# FSR_Array_Sch.net
KiCad netlist of a schematic drawn in Altium Designer
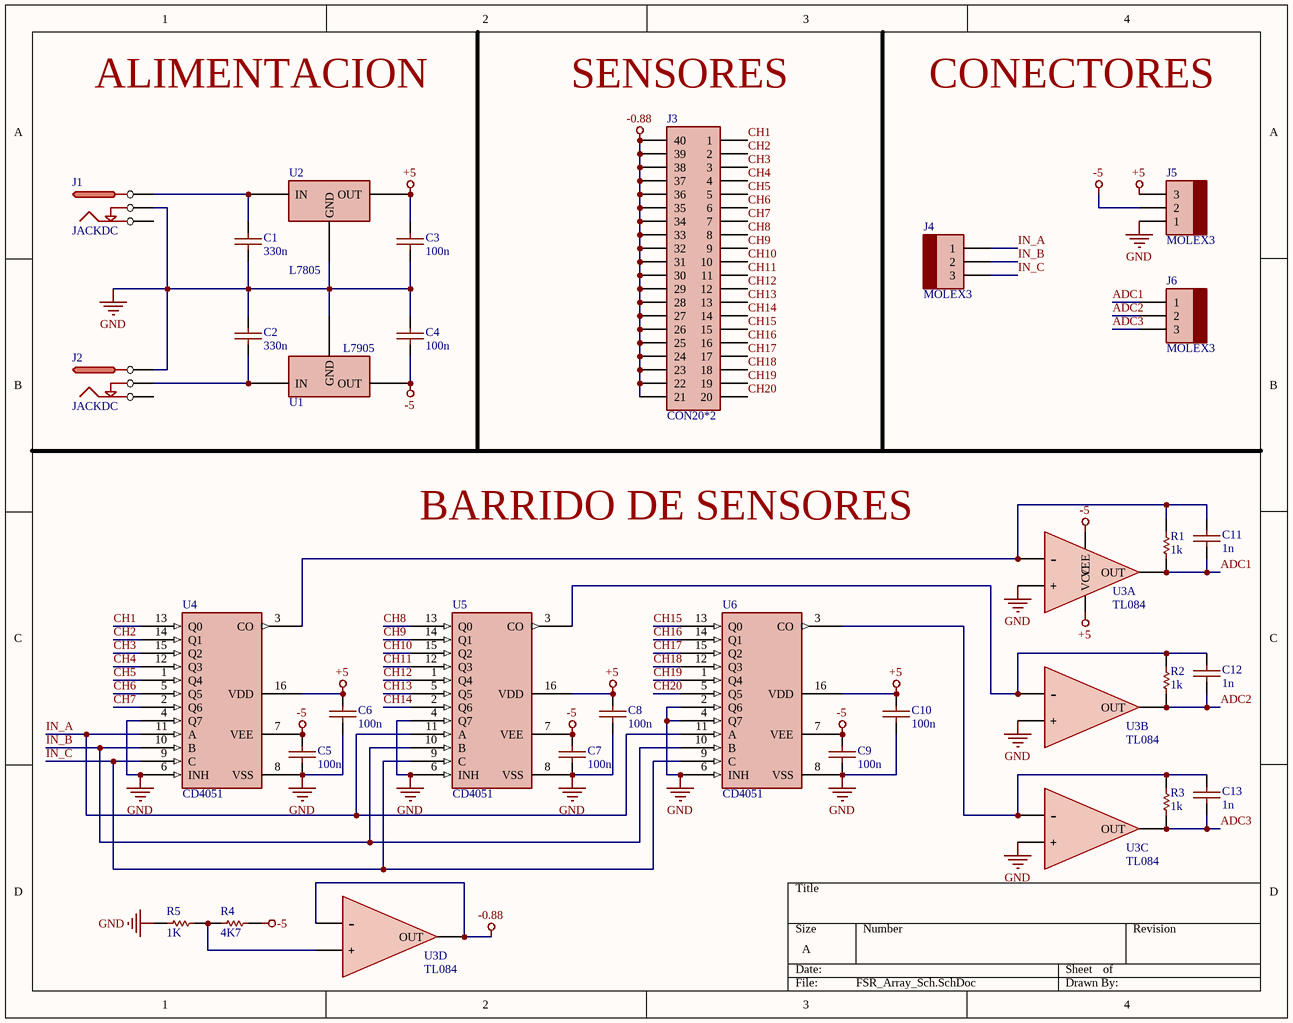
[diagram p0: FSR_Array_Sch.SchDoc]

(export (version "E")
  (design (tool "Eeschema 10.0.6"))
  (components
    (comp (ref "C1") (value "330n") (footprint "0805") (libsource (lib "SchLib_Recinto") (part "CAP")))
    (comp (ref "C2") (value "330n") (footprint "0805") (libsource (lib "SchLib_Recinto") (part "CAP")))
    (comp (ref "C3") (value "100n") (footprint "0805") (libsource (lib "SchLib_Recinto") (part "CAP")))
    (comp (ref "C4") (value "100n") (footprint "0805") (libsource (lib "SchLib_Recinto") (part "CAP")))
    (comp (ref "C5") (value "100n") (footprint "0805") (libsource (lib "SchLib_Recinto") (part "CAP")))
    (comp (ref "C6") (value "100n") (footprint "0805") (libsource (lib "SchLib_Recinto") (part "CAP")))
    (comp (ref "C7") (value "100n") (footprint "0805") (libsource (lib "SchLib_Recinto") (part "CAP")))
    (comp (ref "C8") (value "100n") (footprint "0805") (libsource (lib "SchLib_Recinto") (part "CAP")))
    (comp (ref "C9") (value "100n") (footprint "0805") (libsource (lib "SchLib_Recinto") (part "CAP")))
    (comp (ref "C10") (value "100n") (footprint "0805") (libsource (lib "SchLib_Recinto") (part "CAP")))
    (comp (ref "C11") (value "1n") (footprint "0805") (libsource (lib "SchLib_Recinto") (part "CAP")))
    (comp (ref "C12") (value "1n") (footprint "0805") (libsource (lib "SchLib_Recinto") (part "CAP")))
    (comp (ref "C13") (value "1n") (footprint "0805") (libsource (lib "SchLib_Recinto") (part "CAP")))
    (comp (ref "J1") (value "JACKDC") (footprint "JACKDC") (libsource (lib "SchLib_Recinto") (part "JACKDC")))
    (comp (ref "J2") (value "JACKDC") (footprint "JACKDC") (libsource (lib "SchLib_Recinto") (part "JACKDC")))
    (comp (ref "J3")
      (value "CON20*2")
      (footprint "SIP20*2")
      (libsource (lib "SchLib_Recinto") (part "CON20*2"))
    )
    (comp (ref "J4") (value "MOLEX3") (footprint "MOLEX3") (libsource (lib "SchLib_Recinto") (part "MOLEX3")))
    (comp (ref "J5") (value "MOLEX3") (footprint "MOLEX3") (libsource (lib "") (part "MOLEX3_2")))
    (comp (ref "J6") (value "MOLEX3") (footprint "MOLEX3") (libsource (lib "") (part "MOLEX3_1")))
    (comp (ref "R1") (value "1k") (footprint "0805") (libsource (lib "SchLib_Recinto") (part "RES")))
    (comp (ref "R2") (value "1k") (footprint "0805") (libsource (lib "SchLib_Recinto") (part "RES")))
    (comp (ref "R3") (value "1k") (footprint "0805") (libsource (lib "SchLib_Recinto") (part "RES")))
    (comp (ref "R4") (value "4K7") (footprint "0805") (libsource (lib "SchLib_Recinto") (part "RES")))
    (comp (ref "R5") (value "1K") (footprint "0805") (libsource (lib "SchLib_Recinto") (part "RES")))
    (comp (ref "U1")
      (value "L7905")
      (footprint "TO-220 V")
      (libsource (lib "SchLib_Recinto") (part "LM7905"))
    )
    (comp (ref "U2") (value "L7805") (footprint "TO-220 V") (libsource (lib "SchLib_Recinto") (part "L7805")))
    (comp (ref "U3") (value "TL084") (footprint "SOIC-14") (libsource (lib "SchLib_Recinto") (part "TL084")))
    (comp (ref "U4") (value "CD4051") (footprint "CD4051") (libsource (lib "SchLib_Recinto") (part "CD4051")))
    (comp (ref "U5") (value "CD4051") (footprint "CD4051") (libsource (lib "SchLib_Recinto") (part "CD4051")))
    (comp (ref "U6") (value "CD4051") (footprint "CD4051") (libsource (lib "SchLib_Recinto") (part "CD4051")))
  )
  (nets
    (net (code "1") (name "+5") (class "Default")
      (node (ref "C10") (pin "1") (pintype "passive"))
      (node (ref "C3") (pin "1") (pintype "passive"))
      (node (ref "C6") (pin "1") (pintype "passive"))
      (node (ref "C8") (pin "1") (pintype "passive"))
      (node (ref "J5") (pin "3") (pinfunction "3_3") (pintype "passive"))
      (node (ref "U2") (pin "3") (pinfunction "OUT_3") (pintype "passive"))
      (node (ref "U3") (pin "4") (pinfunction "VCC_4") (pintype "passive"))
      (node (ref "U4") (pin "16") (pinfunction "VDD_16") (pintype "power_in"))
      (node (ref "U5") (pin "16") (pinfunction "VDD_16") (pintype "power_in"))
      (node (ref "U6") (pin "16") (pinfunction "VDD_16") (pintype "power_in"))
    )
    (net (code "2") (name "-0.88") (class "Default")
      (node (ref "J3") (pin "21") (pinfunction "21_21") (pintype "passive"))
      (node (ref "J3") (pin "22") (pinfunction "22_22") (pintype "passive"))
      (node (ref "J3") (pin "23") (pinfunction "23_23") (pintype "passive"))
      (node (ref "J3") (pin "24") (pinfunction "24_24") (pintype "passive"))
      (node (ref "J3") (pin "25") (pinfunction "25_25") (pintype "passive"))
      (node (ref "J3") (pin "26") (pinfunction "26_26") (pintype "passive"))
      (node (ref "J3") (pin "27") (pinfunction "27_27") (pintype "passive"))
      (node (ref "J3") (pin "28") (pinfunction "28_28") (pintype "passive"))
      (node (ref "J3") (pin "29") (pinfunction "29_29") (pintype "passive"))
      (node (ref "J3") (pin "30") (pinfunction "30_30") (pintype "passive"))
      (node (ref "J3") (pin "31") (pinfunction "31_31") (pintype "passive"))
      (node (ref "J3") (pin "32") (pinfunction "32_32") (pintype "passive"))
      (node (ref "J3") (pin "33") (pinfunction "33_33") (pintype "passive"))
      (node (ref "J3") (pin "34") (pinfunction "34_34") (pintype "passive"))
      (node (ref "J3") (pin "35") (pinfunction "35_35") (pintype "passive"))
      (node (ref "J3") (pin "36") (pinfunction "36_36") (pintype "passive"))
      (node (ref "J3") (pin "37") (pinfunction "37_37") (pintype "passive"))
      (node (ref "J3") (pin "38") (pinfunction "38_38") (pintype "passive"))
      (node (ref "J3") (pin "39") (pinfunction "39_39") (pintype "passive"))
      (node (ref "J3") (pin "40") (pinfunction "40_40") (pintype "passive"))
      (node (ref "U3") (pin "13") (pinfunction "-_13") (pintype "passive"))
      (node (ref "U3") (pin "14") (pinfunction "OUT_14") (pintype "passive"))
    )
    (net (code "3") (name "-5") (class "Default")
      (node (ref "C4") (pin "2") (pintype "passive"))
      (node (ref "C5") (pin "1") (pintype "passive"))
      (node (ref "C7") (pin "1") (pintype "passive"))
      (node (ref "C9") (pin "1") (pintype "passive"))
      (node (ref "J5") (pin "2") (pinfunction "2_2") (pintype "passive"))
      (node (ref "R4") (pin "1") (pinfunction "1_1") (pintype "passive"))
      (node (ref "U1") (pin "3") (pinfunction "OUT_3") (pintype "passive"))
      (node (ref "U3") (pin "11") (pinfunction "VEE_11") (pintype "passive"))
      (node (ref "U4") (pin "7") (pinfunction "VEE_7") (pintype "power_in"))
      (node (ref "U5") (pin "7") (pinfunction "VEE_7") (pintype "power_in"))
      (node (ref "U6") (pin "7") (pinfunction "VEE_7") (pintype "power_in"))
    )
    (net (code "4") (name "/ADC1") (class "Default")
      (node (ref "C11") (pin "2") (pintype "passive"))
      (node (ref "J6") (pin "1") (pinfunction "1_1") (pintype "passive"))
      (node (ref "R1") (pin "1") (pinfunction "1_1") (pintype "passive"))
      (node (ref "U3") (pin "1") (pinfunction "OUT_1") (pintype "passive"))
    )
    (net (code "5") (name "/ADC2") (class "Default")
      (node (ref "C12") (pin "2") (pintype "passive"))
      (node (ref "J6") (pin "2") (pinfunction "2_2") (pintype "passive"))
      (node (ref "R2") (pin "1") (pinfunction "1_1") (pintype "passive"))
      (node (ref "U3") (pin "7") (pinfunction "OUT_7") (pintype "passive"))
    )
    (net (code "6") (name "/ADC3") (class "Default")
      (node (ref "C13") (pin "2") (pintype "passive"))
      (node (ref "J6") (pin "3") (pinfunction "3_3") (pintype "passive"))
      (node (ref "R3") (pin "1") (pinfunction "1_1") (pintype "passive"))
      (node (ref "U3") (pin "8") (pinfunction "OUT_8") (pintype "passive"))
    )
    (net (code "7") (name "/CH1") (class "Default")
      (node (ref "J3") (pin "1") (pinfunction "1_1") (pintype "passive"))
      (node (ref "U4") (pin "13") (pinfunction "Q0_13") (pintype "input"))
    )
    (net (code "8") (name "/CH2") (class "Default")
      (node (ref "J3") (pin "2") (pinfunction "2_2") (pintype "passive"))
      (node (ref "U4") (pin "14") (pinfunction "Q1_14") (pintype "input"))
    )
    (net (code "9") (name "/CH3") (class "Default")
      (node (ref "J3") (pin "3") (pinfunction "3_3") (pintype "passive"))
      (node (ref "U4") (pin "15") (pinfunction "Q2_15") (pintype "input"))
    )
    (net (code "10") (name "/CH4") (class "Default")
      (node (ref "J3") (pin "4") (pinfunction "4_4") (pintype "passive"))
      (node (ref "U4") (pin "12") (pinfunction "Q3_12") (pintype "input"))
    )
    (net (code "11") (name "/CH5") (class "Default")
      (node (ref "J3") (pin "5") (pinfunction "5_5") (pintype "passive"))
      (node (ref "U4") (pin "1") (pinfunction "Q4_1") (pintype "input"))
    )
    (net (code "12") (name "/CH6") (class "Default")
      (node (ref "J3") (pin "6") (pinfunction "6_6") (pintype "passive"))
      (node (ref "U4") (pin "5") (pinfunction "Q5_5") (pintype "input"))
    )
    (net (code "13") (name "/CH7") (class "Default")
      (node (ref "J3") (pin "7") (pinfunction "7_7") (pintype "passive"))
      (node (ref "U4") (pin "2") (pinfunction "Q6_2") (pintype "input"))
    )
    (net (code "14") (name "/CH8") (class "Default")
      (node (ref "J3") (pin "8") (pinfunction "8_8") (pintype "passive"))
      (node (ref "U5") (pin "13") (pinfunction "Q0_13") (pintype "input"))
    )
    (net (code "15") (name "/CH9") (class "Default")
      (node (ref "J3") (pin "9") (pinfunction "9_9") (pintype "passive"))
      (node (ref "U5") (pin "14") (pinfunction "Q1_14") (pintype "input"))
    )
    (net (code "16") (name "/CH10") (class "Default")
      (node (ref "J3") (pin "10") (pinfunction "10_10") (pintype "passive"))
      (node (ref "U5") (pin "15") (pinfunction "Q2_15") (pintype "input"))
    )
    (net (code "17") (name "/CH11") (class "Default")
      (node (ref "J3") (pin "11") (pinfunction "11_11") (pintype "passive"))
      (node (ref "U5") (pin "12") (pinfunction "Q3_12") (pintype "input"))
    )
    (net (code "18") (name "/CH12") (class "Default")
      (node (ref "J3") (pin "12") (pinfunction "12_12") (pintype "passive"))
      (node (ref "U5") (pin "1") (pinfunction "Q4_1") (pintype "input"))
    )
    (net (code "19") (name "/CH13") (class "Default")
      (node (ref "J3") (pin "13") (pinfunction "13_13") (pintype "passive"))
      (node (ref "U5") (pin "5") (pinfunction "Q5_5") (pintype "input"))
    )
    (net (code "20") (name "/CH14") (class "Default")
      (node (ref "J3") (pin "14") (pinfunction "14_14") (pintype "passive"))
      (node (ref "U5") (pin "2") (pinfunction "Q6_2") (pintype "input"))
    )
    (net (code "21") (name "/CH15") (class "Default")
      (node (ref "J3") (pin "15") (pinfunction "15_15") (pintype "passive"))
      (node (ref "U6") (pin "13") (pinfunction "Q0_13") (pintype "input"))
    )
    (net (code "22") (name "/CH16") (class "Default")
      (node (ref "J3") (pin "16") (pinfunction "16_16") (pintype "passive"))
      (node (ref "U6") (pin "14") (pinfunction "Q1_14") (pintype "input"))
    )
    (net (code "23") (name "/CH17") (class "Default")
      (node (ref "J3") (pin "17") (pinfunction "17_17") (pintype "passive"))
      (node (ref "U6") (pin "15") (pinfunction "Q2_15") (pintype "input"))
    )
    (net (code "24") (name "/CH18") (class "Default")
      (node (ref "J3") (pin "18") (pinfunction "18_18") (pintype "passive"))
      (node (ref "U6") (pin "12") (pinfunction "Q3_12") (pintype "input"))
    )
    (net (code "25") (name "/CH19") (class "Default")
      (node (ref "J3") (pin "19") (pinfunction "19_19") (pintype "passive"))
      (node (ref "U6") (pin "1") (pinfunction "Q4_1") (pintype "input"))
    )
    (net (code "26") (name "/CH20") (class "Default")
      (node (ref "J3") (pin "20") (pinfunction "20_20") (pintype "passive"))
      (node (ref "U6") (pin "5") (pinfunction "Q5_5") (pintype "input"))
    )
    (net (code "27") (name "/IN_A") (class "Default")
      (node (ref "J4") (pin "1") (pinfunction "1_1") (pintype "passive"))
      (node (ref "U4") (pin "11") (pinfunction "A_11") (pintype "input"))
      (node (ref "U5") (pin "11") (pinfunction "A_11") (pintype "input"))
      (node (ref "U6") (pin "11") (pinfunction "A_11") (pintype "input"))
    )
    (net (code "28") (name "/IN_B") (class "Default")
      (node (ref "J4") (pin "2") (pinfunction "2_2") (pintype "passive"))
      (node (ref "U4") (pin "10") (pinfunction "B_10") (pintype "input"))
      (node (ref "U5") (pin "10") (pinfunction "B_10") (pintype "input"))
      (node (ref "U6") (pin "10") (pinfunction "B_10") (pintype "input"))
    )
    (net (code "29") (name "/IN_C") (class "Default")
      (node (ref "J4") (pin "3") (pinfunction "3_3") (pintype "passive"))
      (node (ref "U4") (pin "9") (pinfunction "C_9") (pintype "input"))
      (node (ref "U5") (pin "9") (pinfunction "C_9") (pintype "input"))
      (node (ref "U6") (pin "9") (pinfunction "C_9") (pintype "input"))
    )
    (net (code "30") (name "GND") (class "Default")
      (node (ref "C1") (pin "2") (pintype "passive"))
      (node (ref "C10") (pin "2") (pintype "passive"))
      (node (ref "C2") (pin "1") (pintype "passive"))
      (node (ref "C3") (pin "2") (pintype "passive"))
      (node (ref "C4") (pin "1") (pintype "passive"))
      (node (ref "C5") (pin "2") (pintype "passive"))
      (node (ref "C6") (pin "2") (pintype "passive"))
      (node (ref "C7") (pin "2") (pintype "passive"))
      (node (ref "C8") (pin "2") (pintype "passive"))
      (node (ref "C9") (pin "2") (pintype "passive"))
      (node (ref "J1") (pin "2") (pinfunction "2_2") (pintype "passive"))
      (node (ref "J2") (pin "1") (pinfunction "1_1") (pintype "passive"))
      (node (ref "J5") (pin "1") (pinfunction "1_1") (pintype "passive"))
      (node (ref "R5") (pin "1") (pinfunction "1_1") (pintype "passive"))
      (node (ref "U1") (pin "1") (pinfunction "GND_1") (pintype "passive"))
      (node (ref "U2") (pin "2") (pinfunction "GND_2") (pintype "passive"))
      (node (ref "U3") (pin "10") (pinfunction "+_10") (pintype "passive"))
      (node (ref "U3") (pin "3") (pinfunction "+_3") (pintype "passive"))
      (node (ref "U3") (pin "5") (pinfunction "+_5") (pintype "passive"))
      (node (ref "U4") (pin "4") (pinfunction "Q7_4") (pintype "input"))
      (node (ref "U4") (pin "6") (pinfunction "INH_6") (pintype "input"))
      (node (ref "U4") (pin "8") (pinfunction "VSS_8") (pintype "power_in"))
      (node (ref "U5") (pin "4") (pinfunction "Q7_4") (pintype "input"))
      (node (ref "U5") (pin "6") (pinfunction "INH_6") (pintype "input"))
      (node (ref "U5") (pin "8") (pinfunction "VSS_8") (pintype "power_in"))
      (node (ref "U6") (pin "2") (pinfunction "Q6_2") (pintype "input"))
      (node (ref "U6") (pin "4") (pinfunction "Q7_4") (pintype "input"))
      (node (ref "U6") (pin "6") (pinfunction "INH_6") (pintype "input"))
      (node (ref "U6") (pin "8") (pinfunction "VSS_8") (pintype "power_in"))
    )
    (net (code "31") (name "Net-(U1-IN)") (class "Default")
      (node (ref "C2") (pin "2") (pintype "passive"))
      (node (ref "J2") (pin "2") (pinfunction "2_2") (pintype "passive"))
      (node (ref "U1") (pin "2") (pinfunction "IN_2") (pintype "passive"))
    )
    (net (code "32") (name "Net-(U2-IN)") (class "Default")
      (node (ref "C1") (pin "1") (pintype "passive"))
      (node (ref "J1") (pin "1") (pinfunction "1_1") (pintype "passive"))
      (node (ref "U2") (pin "1") (pinfunction "IN_1") (pintype "passive"))
    )
    (net (code "33") (name "Net-(U3A--)") (class "Default")
      (node (ref "C11") (pin "1") (pintype "passive"))
      (node (ref "R1") (pin "2") (pinfunction "2_2") (pintype "passive"))
      (node (ref "U3") (pin "2") (pinfunction "-_2") (pintype "passive"))
      (node (ref "U4") (pin "3") (pinfunction "CO_3") (pintype "output"))
    )
    (net (code "34") (name "Net-(U3B--)") (class "Default")
      (node (ref "C12") (pin "1") (pintype "passive"))
      (node (ref "R2") (pin "2") (pinfunction "2_2") (pintype "passive"))
      (node (ref "U3") (pin "6") (pinfunction "-_6") (pintype "passive"))
      (node (ref "U5") (pin "3") (pinfunction "CO_3") (pintype "output"))
    )
    (net (code "35") (name "Net-(U3C--)") (class "Default")
      (node (ref "C13") (pin "1") (pintype "passive"))
      (node (ref "R3") (pin "2") (pinfunction "2_2") (pintype "passive"))
      (node (ref "U3") (pin "9") (pinfunction "-_9") (pintype "passive"))
      (node (ref "U6") (pin "3") (pinfunction "CO_3") (pintype "output"))
    )
    (net (code "36") (name "Net-(U3D-+)") (class "Default")
      (node (ref "R4") (pin "2") (pinfunction "2_2") (pintype "passive"))
      (node (ref "R5") (pin "2") (pinfunction "2_2") (pintype "passive"))
      (node (ref "U3") (pin "12") (pinfunction "+_12") (pintype "passive"))
    )
    (net (code "37") (name "unconnected-(J1-Pad3)") (class "Default")
      (node (ref "J1") (pin "3") (pinfunction "3_3") (pintype "passive"))
    )
    (net (code "38") (name "unconnected-(J2-Pad3)") (class "Default")
      (node (ref "J2") (pin "3") (pinfunction "3_3") (pintype "passive"))
    )
  )
)
